# AUX_Analog_IO.net
KiCad netlist of a schematic drawn in Altium Designer
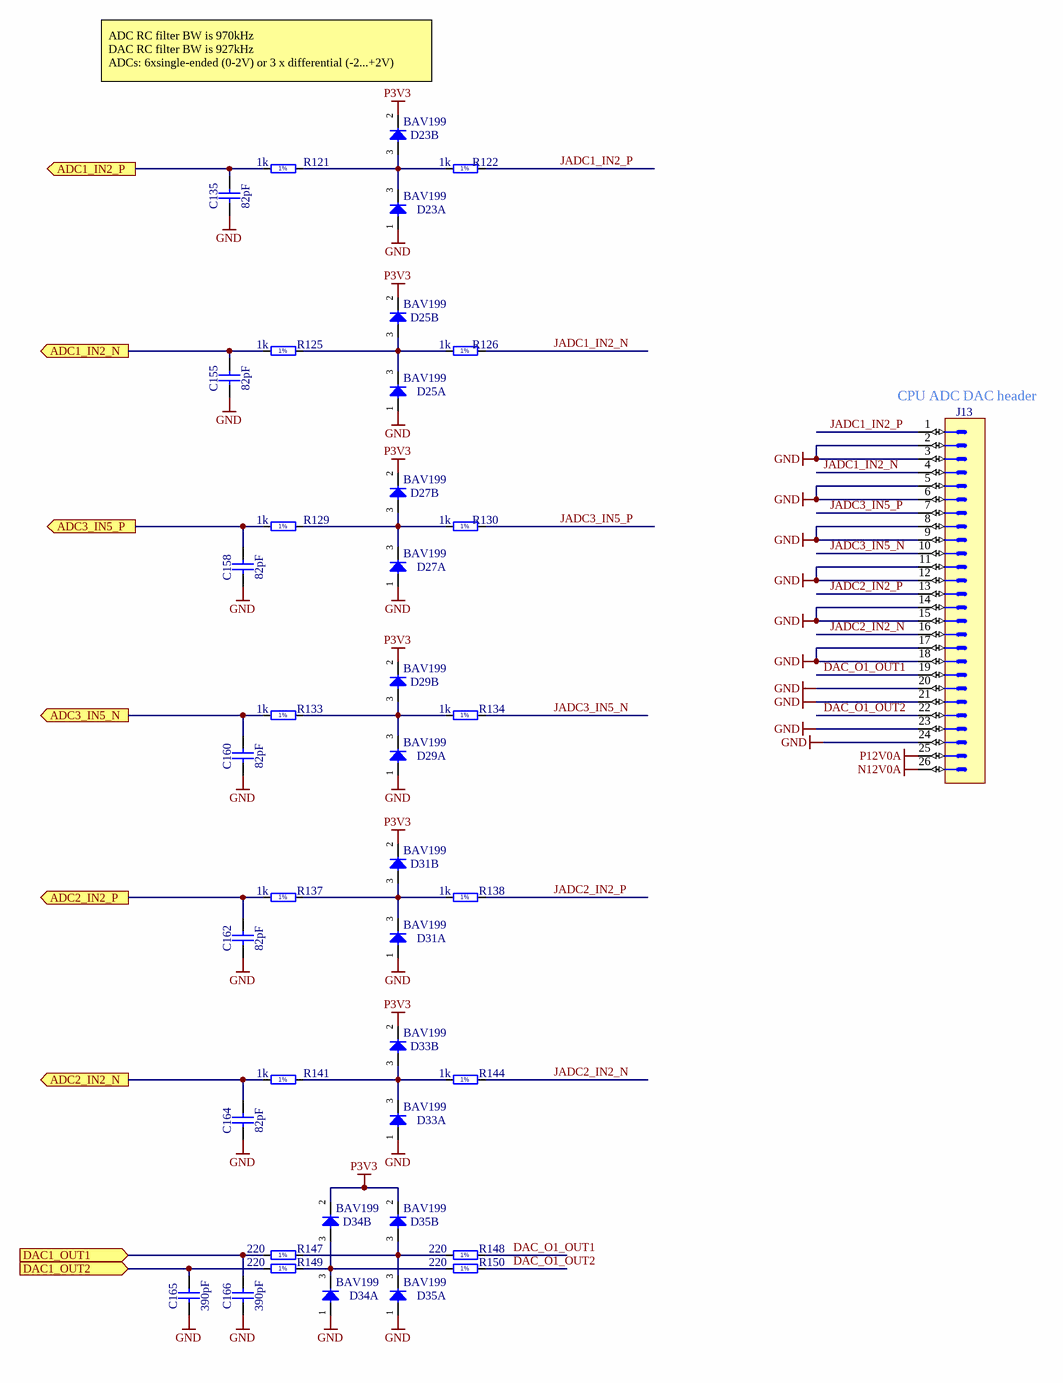
[diagram p0: AUX_Analog_IO.SchDoc]

(export (version "E")
  (design (tool "Eeschema 10.0.6"))
  (components
    (comp (ref "C135")
      (value "82pF")
      (footprint "CAPC1608X87N")
      (description "Non-polarised capacitor")
      (fields
        (field (name "PART NUMBER") "CC0603_82PF_50V_5%_NP0")
        (field (name "VOLTAGE") "50V")
        (field (name "AUTHOR") "CERN DEM JLC")
      )
      (libsource (lib "Capacitors") (part "Capacitor - non polarized"))
    )
    (comp (ref "C155")
      (value "82pF")
      (footprint "CAPC1608X87N")
      (description "Non-polarised capacitor")
      (fields
        (field (name "PART NUMBER") "CC0603_82PF_50V_5%_NP0")
        (field (name "VOLTAGE") "50V")
        (field (name "AUTHOR") "CERN DEM JLC")
      )
      (libsource (lib "Capacitors") (part "Capacitor - non polarized"))
    )
    (comp (ref "C158")
      (value "82pF")
      (footprint "CAPC1608X87N")
      (description "Non-polarised capacitor")
      (fields
        (field (name "PART NUMBER") "CC0603_82PF_50V_5%_NP0")
        (field (name "VOLTAGE") "50V")
        (field (name "AUTHOR") "CERN DEM JLC")
      )
      (libsource (lib "Capacitors") (part "Capacitor - non polarized"))
    )
    (comp (ref "C160")
      (value "82pF")
      (footprint "CAPC1608X87N")
      (description "Non-polarised capacitor")
      (fields
        (field (name "PART NUMBER") "CC0603_82PF_50V_5%_NP0")
        (field (name "VOLTAGE") "50V")
        (field (name "AUTHOR") "CERN DEM JLC")
      )
      (libsource (lib "Capacitors") (part "Capacitor - non polarized"))
    )
    (comp (ref "C162")
      (value "82pF")
      (footprint "CAPC1608X87N")
      (description "Non-polarised capacitor")
      (fields
        (field (name "PART NUMBER") "CC0603_82PF_50V_5%_NP0")
        (field (name "VOLTAGE") "50V")
        (field (name "AUTHOR") "CERN DEM JLC")
      )
      (libsource (lib "Capacitors") (part "Capacitor - non polarized"))
    )
    (comp (ref "C164")
      (value "82pF")
      (footprint "CAPC1608X87N")
      (description "Non-polarised capacitor")
      (fields
        (field (name "PART NUMBER") "CC0603_82PF_50V_5%_NP0")
        (field (name "VOLTAGE") "50V")
        (field (name "AUTHOR") "CERN DEM JLC")
      )
      (libsource (lib "Capacitors") (part "Capacitor - non polarized"))
    )
    (comp (ref "C165")
      (value "390pF")
      (footprint "CAPC1608X87N")
      (description "Non-polarised capacitor")
      (fields
        (field (name "PART NUMBER") "CC0603_390PF_50V_5%_NP0")
        (field (name "VOLTAGE") "50V")
        (field (name "AUTHOR") "CERN DEM JLC")
      )
      (libsource (lib "Capacitors") (part "Capacitor - non polarized"))
    )
    (comp (ref "C166")
      (value "390pF")
      (footprint "CAPC1608X87N")
      (description "Non-polarised capacitor")
      (fields
        (field (name "PART NUMBER") "CC0603_390PF_50V_5%_NP0")
        (field (name "VOLTAGE") "50V")
        (field (name "AUTHOR") "CERN DEM JLC")
      )
      (libsource (lib "Capacitors") (part "Capacitor - non polarized"))
    )
    (comp (ref "D23")
      (value "BAV199")
      (footprint "SOT95P240X110-3N")
      (description "Serial Diode")
      (fields
        (field (name "VOLTAGE") "75V")
        (field (name "POWER") "250mW")
        (field (name "AUTHOR") "CERN DEM JMW")
      )
      (libsource (lib "ICs And Semiconductors") (part "Diode x2 A1C3_A3C2"))
    )
    (comp (ref "D25")
      (value "BAV199")
      (footprint "SOT95P240X110-3N")
      (description "Serial Diode")
      (fields
        (field (name "VOLTAGE") "75V")
        (field (name "POWER") "250mW")
        (field (name "AUTHOR") "CERN DEM JMW")
      )
      (libsource (lib "ICs And Semiconductors") (part "Diode x2 A1C3_A3C2"))
    )
    (comp (ref "D27")
      (value "BAV199")
      (footprint "SOT95P240X110-3N")
      (description "Serial Diode")
      (fields
        (field (name "VOLTAGE") "75V")
        (field (name "POWER") "250mW")
        (field (name "AUTHOR") "CERN DEM JMW")
      )
      (libsource (lib "ICs And Semiconductors") (part "Diode x2 A1C3_A3C2"))
    )
    (comp (ref "D29")
      (value "BAV199")
      (footprint "SOT95P240X110-3N")
      (description "Serial Diode")
      (fields
        (field (name "VOLTAGE") "75V")
        (field (name "POWER") "250mW")
        (field (name "AUTHOR") "CERN DEM JMW")
      )
      (libsource (lib "ICs And Semiconductors") (part "Diode x2 A1C3_A3C2"))
    )
    (comp (ref "D31")
      (value "BAV199")
      (footprint "SOT95P240X110-3N")
      (description "Serial Diode")
      (fields
        (field (name "VOLTAGE") "75V")
        (field (name "POWER") "250mW")
        (field (name "AUTHOR") "CERN DEM JMW")
      )
      (libsource (lib "ICs And Semiconductors") (part "Diode x2 A1C3_A3C2"))
    )
    (comp (ref "D33")
      (value "BAV199")
      (footprint "SOT95P240X110-3N")
      (description "Serial Diode")
      (fields
        (field (name "VOLTAGE") "75V")
        (field (name "POWER") "250mW")
        (field (name "AUTHOR") "CERN DEM JMW")
      )
      (libsource (lib "ICs And Semiconductors") (part "Diode x2 A1C3_A3C2"))
    )
    (comp (ref "D34")
      (value "BAV199")
      (footprint "SOT95P240X110-3N")
      (description "Serial Diode")
      (fields
        (field (name "VOLTAGE") "75V")
        (field (name "POWER") "250mW")
        (field (name "AUTHOR") "CERN DEM JMW")
      )
      (libsource (lib "ICs And Semiconductors") (part "Diode x2 A1C3_A3C2"))
    )
    (comp (ref "D35")
      (value "BAV199")
      (footprint "SOT95P240X110-3N")
      (description "Serial Diode")
      (fields
        (field (name "VOLTAGE") "75V")
        (field (name "POWER") "250mW")
        (field (name "AUTHOR") "CERN DEM JMW")
      )
      (libsource (lib "ICs And Semiconductors") (part "Diode x2 A1C3_A3C2"))
    )
    (comp (ref "J13")
      (value "Use original!")
      (footprint "3M_N2526-6002RB")
      (description "Connector 26 Male")
      (fields
        (field (name "PART NUMBER") "Use original! 3M_N2526-6002RB")
        (field (name "MANUFACTURER") "3M")
        (field (name "AUTHOR") "CERN DEM JLC")
      )
      (libsource (lib "Connectors") (part "Connector 26 Male"))
    )
    (comp (ref "R121")
      (value "1k")
      (footprint "RESC1608X55N")
      (description "Resistor - 1%")
      (fields
        (field (name "PART NUMBER") "R0603_1K_1%_0.1W_100PPM")
        (field (name "POWER") "0.1W")
        (field (name "AUTHOR") "CERN DEM JLC")
      )
      (libsource (lib "Resistors") (part "Resistor - 1%"))
    )
    (comp (ref "R122")
      (value "1k")
      (footprint "RESC1608X55N")
      (description "Resistor - 1%")
      (fields
        (field (name "PART NUMBER") "R0603_1K_1%_0.1W_100PPM")
        (field (name "POWER") "0.1W")
        (field (name "AUTHOR") "CERN DEM JLC")
      )
      (libsource (lib "Resistors") (part "Resistor - 1%"))
    )
    (comp (ref "R125")
      (value "1k")
      (footprint "RESC1608X55N")
      (description "Resistor - 1%")
      (fields
        (field (name "PART NUMBER") "R0603_1K_1%_0.1W_100PPM")
        (field (name "POWER") "0.1W")
        (field (name "AUTHOR") "CERN DEM JLC")
      )
      (libsource (lib "Resistors") (part "Resistor - 1%"))
    )
    (comp (ref "R126")
      (value "1k")
      (footprint "RESC1608X55N")
      (description "Resistor - 1%")
      (fields
        (field (name "PART NUMBER") "R0603_1K_1%_0.1W_100PPM")
        (field (name "POWER") "0.1W")
        (field (name "AUTHOR") "CERN DEM JLC")
      )
      (libsource (lib "Resistors") (part "Resistor - 1%"))
    )
    (comp (ref "R129")
      (value "1k")
      (footprint "RESC1608X55N")
      (description "Resistor - 1%")
      (fields
        (field (name "PART NUMBER") "R0603_1K_1%_0.1W_100PPM")
        (field (name "POWER") "0.1W")
        (field (name "AUTHOR") "CERN DEM JLC")
      )
      (libsource (lib "Resistors") (part "Resistor - 1%"))
    )
    (comp (ref "R130")
      (value "1k")
      (footprint "RESC1608X55N")
      (description "Resistor - 1%")
      (fields
        (field (name "PART NUMBER") "R0603_1K_1%_0.1W_100PPM")
        (field (name "POWER") "0.1W")
        (field (name "AUTHOR") "CERN DEM JLC")
      )
      (libsource (lib "Resistors") (part "Resistor - 1%"))
    )
    (comp (ref "R133")
      (value "1k")
      (footprint "RESC1608X55N")
      (description "Resistor - 1%")
      (fields
        (field (name "PART NUMBER") "R0603_1K_1%_0.1W_100PPM")
        (field (name "POWER") "0.1W")
        (field (name "AUTHOR") "CERN DEM JLC")
      )
      (libsource (lib "Resistors") (part "Resistor - 1%"))
    )
    (comp (ref "R134")
      (value "1k")
      (footprint "RESC1608X55N")
      (description "Resistor - 1%")
      (fields
        (field (name "PART NUMBER") "R0603_1K_1%_0.1W_100PPM")
        (field (name "POWER") "0.1W")
        (field (name "AUTHOR") "CERN DEM JLC")
      )
      (libsource (lib "Resistors") (part "Resistor - 1%"))
    )
    (comp (ref "R137")
      (value "1k")
      (footprint "RESC1608X55N")
      (description "Resistor - 1%")
      (fields
        (field (name "PART NUMBER") "R0603_1K_1%_0.1W_100PPM")
        (field (name "POWER") "0.1W")
        (field (name "AUTHOR") "CERN DEM JLC")
      )
      (libsource (lib "Resistors") (part "Resistor - 1%"))
    )
    (comp (ref "R138")
      (value "1k")
      (footprint "RESC1608X55N")
      (description "Resistor - 1%")
      (fields
        (field (name "PART NUMBER") "R0603_1K_1%_0.1W_100PPM")
        (field (name "POWER") "0.1W")
        (field (name "AUTHOR") "CERN DEM JLC")
      )
      (libsource (lib "Resistors") (part "Resistor - 1%"))
    )
    (comp (ref "R141")
      (value "1k")
      (footprint "RESC1608X55N")
      (description "Resistor - 1%")
      (fields
        (field (name "PART NUMBER") "R0603_1K_1%_0.1W_100PPM")
        (field (name "POWER") "0.1W")
        (field (name "AUTHOR") "CERN DEM JLC")
      )
      (libsource (lib "Resistors") (part "Resistor - 1%"))
    )
    (comp (ref "R144")
      (value "1k")
      (footprint "RESC1608X55N")
      (description "Resistor - 1%")
      (fields
        (field (name "PART NUMBER") "R0603_1K_1%_0.1W_100PPM")
        (field (name "POWER") "0.1W")
        (field (name "AUTHOR") "CERN DEM JLC")
      )
      (libsource (lib "Resistors") (part "Resistor - 1%"))
    )
    (comp (ref "R147")
      (value "220")
      (footprint "RESC1608X55N")
      (description "Resistor - 1%")
      (fields
        (field (name "PART NUMBER") "R0603_220R_1%_0.1W_100PPM")
        (field (name "POWER") "0.1W")
        (field (name "AUTHOR") "CERN DEM JLC")
      )
      (libsource (lib "Resistors") (part "Resistor - 1%"))
    )
    (comp (ref "R148")
      (value "220")
      (footprint "RESC1608X55N")
      (description "Resistor - 1%")
      (fields
        (field (name "PART NUMBER") "R0603_220R_1%_0.1W_100PPM")
        (field (name "POWER") "0.1W")
        (field (name "AUTHOR") "CERN DEM JLC")
      )
      (libsource (lib "Resistors") (part "Resistor - 1%"))
    )
    (comp (ref "R149")
      (value "220")
      (footprint "RESC1608X55N")
      (description "Resistor - 1%")
      (fields
        (field (name "PART NUMBER") "R0603_220R_1%_0.1W_100PPM")
        (field (name "POWER") "0.1W")
        (field (name "AUTHOR") "CERN DEM JLC")
      )
      (libsource (lib "Resistors") (part "Resistor - 1%"))
    )
    (comp (ref "R150")
      (value "220")
      (footprint "RESC1608X55N")
      (description "Resistor - 1%")
      (fields
        (field (name "PART NUMBER") "R0603_220R_1%_0.1W_100PPM")
        (field (name "POWER") "0.1W")
        (field (name "AUTHOR") "CERN DEM JLC")
      )
      (libsource (lib "Resistors") (part "Resistor - 1%"))
    )
  )
  (nets
    (net (code "1") (name "/ADC1_IN2_N") (class "Default")
      (node (ref "C155") (pin "2") (pinfunction "2_2") (pintype "passive"))
      (node (ref "R125") (pin "1") (pinfunction "1_1") (pintype "passive"))
    )
    (net (code "2") (name "/ADC1_IN2_P") (class "Default")
      (node (ref "C135") (pin "2") (pinfunction "2_2") (pintype "passive"))
      (node (ref "R121") (pin "1") (pinfunction "1_1") (pintype "passive"))
    )
    (net (code "3") (name "/ADC2_IN2_N") (class "Default")
      (node (ref "C164") (pin "2") (pinfunction "2_2") (pintype "passive"))
      (node (ref "R141") (pin "1") (pinfunction "1_1") (pintype "passive"))
    )
    (net (code "4") (name "/ADC2_IN2_P") (class "Default")
      (node (ref "C162") (pin "2") (pinfunction "2_2") (pintype "passive"))
      (node (ref "R137") (pin "1") (pinfunction "1_1") (pintype "passive"))
    )
    (net (code "5") (name "/ADC3_IN5_N") (class "Default")
      (node (ref "C160") (pin "2") (pinfunction "2_2") (pintype "passive"))
      (node (ref "R133") (pin "1") (pinfunction "1_1") (pintype "passive"))
    )
    (net (code "6") (name "/ADC3_IN5_P") (class "Default")
      (node (ref "C158") (pin "2") (pinfunction "2_2") (pintype "passive"))
      (node (ref "R129") (pin "1") (pinfunction "1_1") (pintype "passive"))
    )
    (net (code "7") (name "/DAC1_OUT1") (class "Default")
      (node (ref "C166") (pin "2") (pinfunction "2_2") (pintype "passive"))
      (node (ref "R147") (pin "1") (pinfunction "1_1") (pintype "passive"))
    )
    (net (code "8") (name "/DAC1_OUT2") (class "Default")
      (node (ref "C165") (pin "2") (pinfunction "2_2") (pintype "passive"))
      (node (ref "R149") (pin "1") (pinfunction "1_1") (pintype "passive"))
    )
    (net (code "9") (name "/DAC_O1_OUT1") (class "Default")
      (node (ref "J13") (pin "19") (pinfunction "19_19") (pintype "bidirectional"))
      (node (ref "R148") (pin "2") (pinfunction "2_2") (pintype "passive"))
    )
    (net (code "10") (name "/DAC_O1_OUT2") (class "Default")
      (node (ref "J13") (pin "22") (pinfunction "22_22") (pintype "bidirectional"))
      (node (ref "R150") (pin "2") (pinfunction "2_2") (pintype "passive"))
    )
    (net (code "11") (name "/JADC1_IN2_N") (class "Default")
      (node (ref "J13") (pin "4") (pinfunction "4_4") (pintype "bidirectional"))
      (node (ref "R126") (pin "2") (pinfunction "2_2") (pintype "passive"))
    )
    (net (code "12") (name "/JADC1_IN2_P") (class "Default")
      (node (ref "J13") (pin "1") (pinfunction "1_1") (pintype "bidirectional"))
      (node (ref "R122") (pin "2") (pinfunction "2_2") (pintype "passive"))
    )
    (net (code "13") (name "/JADC2_IN2_N") (class "Default")
      (node (ref "J13") (pin "16") (pinfunction "16_16") (pintype "bidirectional"))
      (node (ref "R144") (pin "2") (pinfunction "2_2") (pintype "passive"))
    )
    (net (code "14") (name "/JADC2_IN2_P") (class "Default")
      (node (ref "J13") (pin "13") (pinfunction "13_13") (pintype "bidirectional"))
      (node (ref "R138") (pin "2") (pinfunction "2_2") (pintype "passive"))
    )
    (net (code "15") (name "/JADC3_IN5_N") (class "Default")
      (node (ref "J13") (pin "10") (pinfunction "10_10") (pintype "bidirectional"))
      (node (ref "R134") (pin "2") (pinfunction "2_2") (pintype "passive"))
    )
    (net (code "16") (name "/JADC3_IN5_P") (class "Default")
      (node (ref "J13") (pin "7") (pinfunction "7_7") (pintype "bidirectional"))
      (node (ref "R130") (pin "2") (pinfunction "2_2") (pintype "passive"))
    )
    (net (code "17") (name "GND") (class "Default")
      (node (ref "C135") (pin "1") (pinfunction "1_1") (pintype "passive"))
      (node (ref "C155") (pin "1") (pinfunction "1_1") (pintype "passive"))
      (node (ref "C158") (pin "1") (pinfunction "1_1") (pintype "passive"))
      (node (ref "C160") (pin "1") (pinfunction "1_1") (pintype "passive"))
      (node (ref "C162") (pin "1") (pinfunction "1_1") (pintype "passive"))
      (node (ref "C164") (pin "1") (pinfunction "1_1") (pintype "passive"))
      (node (ref "C165") (pin "1") (pinfunction "1_1") (pintype "passive"))
      (node (ref "C166") (pin "1") (pinfunction "1_1") (pintype "passive"))
      (node (ref "D23") (pin "1") (pinfunction "A_1") (pintype "passive"))
      (node (ref "D25") (pin "1") (pinfunction "A_1") (pintype "passive"))
      (node (ref "D27") (pin "1") (pinfunction "A_1") (pintype "passive"))
      (node (ref "D29") (pin "1") (pinfunction "A_1") (pintype "passive"))
      (node (ref "D31") (pin "1") (pinfunction "A_1") (pintype "passive"))
      (node (ref "D33") (pin "1") (pinfunction "A_1") (pintype "passive"))
      (node (ref "D34") (pin "1") (pinfunction "A_1") (pintype "passive"))
      (node (ref "D35") (pin "1") (pinfunction "A_1") (pintype "passive"))
      (node (ref "J13") (pin "11") (pinfunction "11_11") (pintype "bidirectional"))
      (node (ref "J13") (pin "12") (pinfunction "12_12") (pintype "bidirectional"))
      (node (ref "J13") (pin "14") (pinfunction "14_14") (pintype "bidirectional"))
      (node (ref "J13") (pin "15") (pinfunction "15_15") (pintype "bidirectional"))
      (node (ref "J13") (pin "17") (pinfunction "17_17") (pintype "bidirectional"))
      (node (ref "J13") (pin "18") (pinfunction "18_18") (pintype "bidirectional"))
      (node (ref "J13") (pin "2") (pinfunction "2_2") (pintype "bidirectional"))
      (node (ref "J13") (pin "20") (pinfunction "20_20") (pintype "bidirectional"))
      (node (ref "J13") (pin "21") (pinfunction "21_21") (pintype "bidirectional"))
      (node (ref "J13") (pin "23") (pinfunction "23_23") (pintype "bidirectional"))
      (node (ref "J13") (pin "24") (pinfunction "24_24") (pintype "bidirectional"))
      (node (ref "J13") (pin "3") (pinfunction "3_3") (pintype "bidirectional"))
      (node (ref "J13") (pin "5") (pinfunction "5_5") (pintype "bidirectional"))
      (node (ref "J13") (pin "6") (pinfunction "6_6") (pintype "bidirectional"))
      (node (ref "J13") (pin "8") (pinfunction "8_8") (pintype "bidirectional"))
      (node (ref "J13") (pin "9") (pinfunction "9_9") (pintype "bidirectional"))
    )
    (net (code "18") (name "N12V0A") (class "Default")
      (node (ref "J13") (pin "26") (pinfunction "26_26") (pintype "bidirectional"))
    )
    (net (code "19") (name "Net-(D23A-COMAC)") (class "Default")
      (node (ref "D23") (pin "3") (pinfunction "COMAC_3") (pintype "passive"))
      (node (ref "R121") (pin "2") (pinfunction "2_2") (pintype "passive"))
      (node (ref "R122") (pin "1") (pinfunction "1_1") (pintype "passive"))
    )
    (net (code "20") (name "Net-(D25A-COMAC)") (class "Default")
      (node (ref "D25") (pin "3") (pinfunction "COMAC_3") (pintype "passive"))
      (node (ref "R125") (pin "2") (pinfunction "2_2") (pintype "passive"))
      (node (ref "R126") (pin "1") (pinfunction "1_1") (pintype "passive"))
    )
    (net (code "21") (name "Net-(D27A-COMAC)") (class "Default")
      (node (ref "D27") (pin "3") (pinfunction "COMAC_3") (pintype "passive"))
      (node (ref "R129") (pin "2") (pinfunction "2_2") (pintype "passive"))
      (node (ref "R130") (pin "1") (pinfunction "1_1") (pintype "passive"))
    )
    (net (code "22") (name "Net-(D29A-COMAC)") (class "Default")
      (node (ref "D29") (pin "3") (pinfunction "COMAC_3") (pintype "passive"))
      (node (ref "R133") (pin "2") (pinfunction "2_2") (pintype "passive"))
      (node (ref "R134") (pin "1") (pinfunction "1_1") (pintype "passive"))
    )
    (net (code "23") (name "Net-(D31A-COMAC)") (class "Default")
      (node (ref "D31") (pin "3") (pinfunction "COMAC_3") (pintype "passive"))
      (node (ref "R137") (pin "2") (pinfunction "2_2") (pintype "passive"))
      (node (ref "R138") (pin "1") (pinfunction "1_1") (pintype "passive"))
    )
    (net (code "24") (name "Net-(D33A-COMAC)") (class "Default")
      (node (ref "D33") (pin "3") (pinfunction "COMAC_3") (pintype "passive"))
      (node (ref "R141") (pin "2") (pinfunction "2_2") (pintype "passive"))
      (node (ref "R144") (pin "1") (pinfunction "1_1") (pintype "passive"))
    )
    (net (code "25") (name "Net-(D34A-COMAC)") (class "Default")
      (node (ref "D34") (pin "3") (pinfunction "COMAC_3") (pintype "passive"))
      (node (ref "R149") (pin "2") (pinfunction "2_2") (pintype "passive"))
      (node (ref "R150") (pin "1") (pinfunction "1_1") (pintype "passive"))
    )
    (net (code "26") (name "Net-(D35A-COMAC)") (class "Default")
      (node (ref "D35") (pin "3") (pinfunction "COMAC_3") (pintype "passive"))
      (node (ref "R147") (pin "2") (pinfunction "2_2") (pintype "passive"))
      (node (ref "R148") (pin "1") (pinfunction "1_1") (pintype "passive"))
    )
    (net (code "27") (name "P3V3") (class "Default")
      (node (ref "D23") (pin "2") (pinfunction "C_2") (pintype "passive"))
      (node (ref "D25") (pin "2") (pinfunction "C_2") (pintype "passive"))
      (node (ref "D27") (pin "2") (pinfunction "C_2") (pintype "passive"))
      (node (ref "D29") (pin "2") (pinfunction "C_2") (pintype "passive"))
      (node (ref "D31") (pin "2") (pinfunction "C_2") (pintype "passive"))
      (node (ref "D33") (pin "2") (pinfunction "C_2") (pintype "passive"))
      (node (ref "D34") (pin "2") (pinfunction "C_2") (pintype "passive"))
      (node (ref "D35") (pin "2") (pinfunction "C_2") (pintype "passive"))
    )
    (net (code "28") (name "P12V0A") (class "Default")
      (node (ref "J13") (pin "25") (pinfunction "25_25") (pintype "bidirectional"))
    )
  )
)
